# sensorev7V.net
KiCad netlist of a schematic drawn in EAGLE
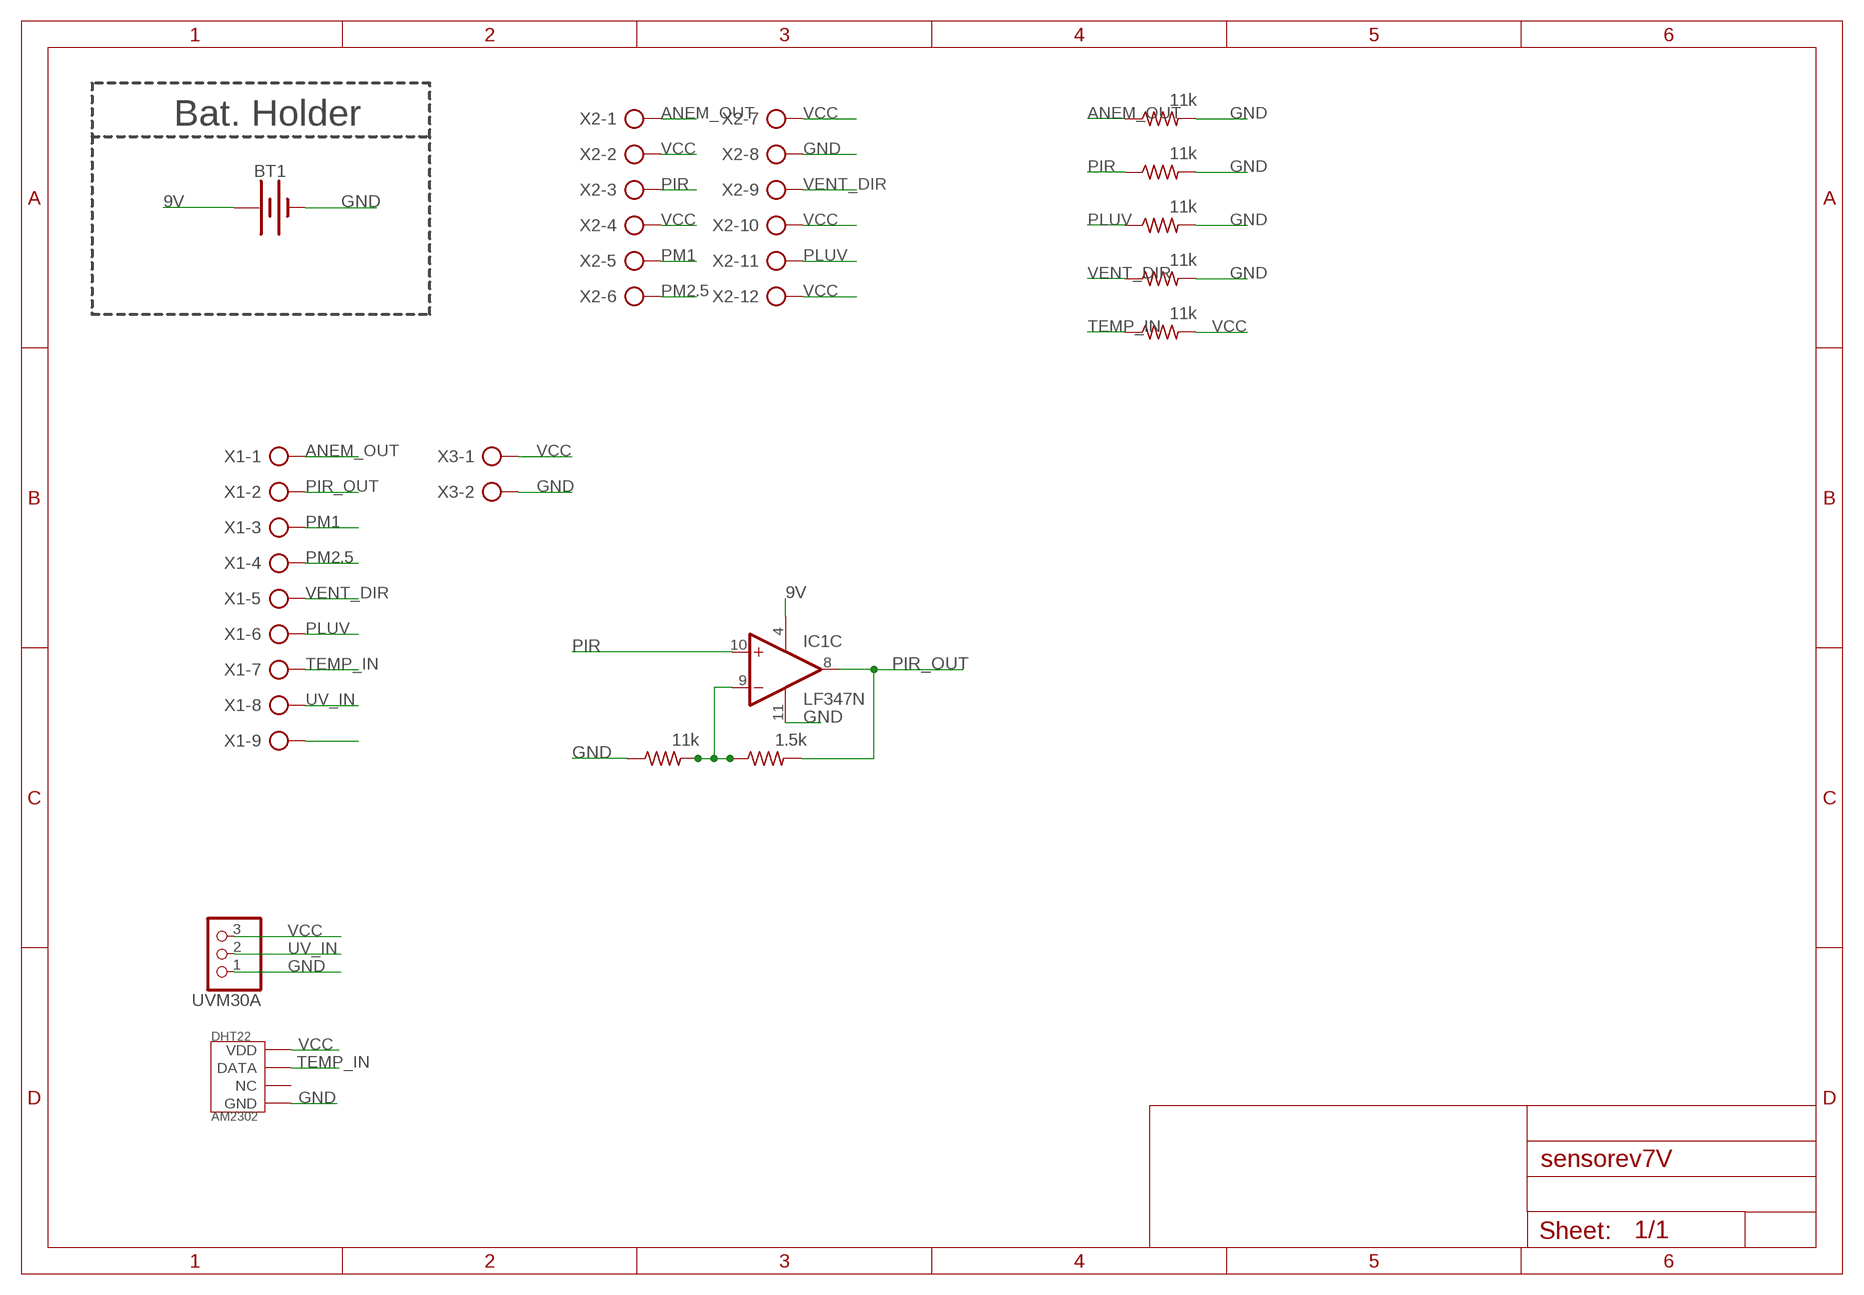
[diagram p0: schematic, sheet 1]

(export (version "E")
  (design (tool "Eeschema 10.0.6"))
  (components
    (comp (ref "BT1")
      (value "BATTERY-9V")
      (footprint "eagle-import:BATTCON_9V")
      (libsource (lib "eagle-import") (part "BATTERY-9V"))
    )
    (comp (ref "DHT22")
      (value "AM2302")
      (footprint "eagle-import:SNR4-2.54-25.0X15.0X7.0MM")
      (libsource (lib "eagle-import") (part "TEM-HUM-AM2302(4P-25.0X15.0MM)"))
    )
    (comp (ref "IC1")
      (value "LF347N")
      (footprint "eagle-import:DIL14")
      (libsource (lib "eagle-import") (part "LF347N"))
    )
    (comp (ref "R1")
      (value "11k")
      (footprint "eagle-import:0204_7")
      (libsource (lib "eagle-import") (part "R-US_0204/7"))
    )
    (comp (ref "R2")
      (value "1.5k")
      (footprint "eagle-import:0204_7")
      (libsource (lib "eagle-import") (part "R-US_0204/7"))
    )
    (comp (ref "R3")
      (value "11k")
      (footprint "eagle-import:0204_7")
      (libsource (lib "eagle-import") (part "R-US_0204/7"))
    )
    (comp (ref "R4")
      (value "11k")
      (footprint "eagle-import:0204_7")
      (libsource (lib "eagle-import") (part "R-US_0204/7"))
    )
    (comp (ref "R5")
      (value "11k")
      (footprint "eagle-import:0204_7")
      (libsource (lib "eagle-import") (part "R-US_0204/7"))
    )
    (comp (ref "R6")
      (value "11k")
      (footprint "eagle-import:0204_7")
      (libsource (lib "eagle-import") (part "R-US_0204/7"))
    )
    (comp (ref "R7")
      (value "11k")
      (footprint "eagle-import:0204_7")
      (libsource (lib "eagle-import") (part "R-US_0204/7"))
    )
    (comp (ref "UVM30A")
      (value "PINHD-1X3/90")
      (footprint "eagle-import:1X03_90")
      (libsource (lib "eagle-import") (part "PINHD-1X3/90"))
    )
    (comp (ref "X1")
      (value "AK500/9")
      (footprint "eagle-import:AK500_9")
      (libsource (lib "eagle-import") (part "AK500/9"))
    )
    (comp (ref "X2")
      (value "AK500/12")
      (footprint "eagle-import:AK500_12")
      (libsource (lib "eagle-import") (part "AK500/12"))
    )
    (comp (ref "X3")
      (value "AK500/2")
      (footprint "eagle-import:AK500_2")
      (libsource (lib "eagle-import") (part "AK500/2"))
    )
  )
  (nets
    (net (code "1") (name "/9V") (class "Default")
      (node (ref "BT1") (pin "+") (pinfunction "+_+") (pintype "power_in"))
      (node (ref "IC1") (pin "4") (pinfunction "V+_4") (pintype "power_in"))
    )
    (net (code "2") (name "/ANEM_OUT") (class "Default")
      (node (ref "R3") (pin "1") (pinfunction "1_1") (pintype "passive"))
      (node (ref "X1") (pin "1") (pinfunction "KL_1") (pintype "passive"))
      (node (ref "X2") (pin "1") (pinfunction "KL_1") (pintype "passive"))
    )
    (net (code "3") (name "/GND") (class "Default")
      (node (ref "BT1") (pin "-") (pinfunction "-_-") (pintype "power_in"))
      (node (ref "DHT22") (pin "P$4") (pinfunction "GND_P$4") (pintype "power_in"))
      (node (ref "IC1") (pin "11") (pinfunction "V-_11") (pintype "power_in"))
      (node (ref "R1") (pin "1") (pinfunction "1_1") (pintype "passive"))
      (node (ref "R3") (pin "2") (pinfunction "2_2") (pintype "passive"))
      (node (ref "R4") (pin "2") (pinfunction "2_2") (pintype "passive"))
      (node (ref "R5") (pin "2") (pinfunction "2_2") (pintype "passive"))
      (node (ref "R6") (pin "2") (pinfunction "2_2") (pintype "passive"))
      (node (ref "UVM30A") (pin "1") (pinfunction "1_1") (pintype "passive"))
      (node (ref "X2") (pin "8") (pinfunction "KL_8") (pintype "passive"))
      (node (ref "X3") (pin "2") (pinfunction "KL_2") (pintype "passive"))
    )
    (net (code "4") (name "/PIR") (class "Default")
      (node (ref "IC1") (pin "10") (pinfunction "+IN_10") (pintype "input"))
      (node (ref "R4") (pin "1") (pinfunction "1_1") (pintype "passive"))
      (node (ref "X2") (pin "3") (pinfunction "KL_3") (pintype "passive"))
    )
    (net (code "5") (name "/PIR_OUT") (class "Default")
      (node (ref "IC1") (pin "8") (pinfunction "OUT_8") (pintype "output"))
      (node (ref "R2") (pin "2") (pinfunction "2_2") (pintype "passive"))
      (node (ref "X1") (pin "2") (pinfunction "KL_2") (pintype "passive"))
    )
    (net (code "6") (name "/PLUV") (class "Default")
      (node (ref "R5") (pin "1") (pinfunction "1_1") (pintype "passive"))
      (node (ref "X1") (pin "6") (pinfunction "KL_6") (pintype "passive"))
      (node (ref "X2") (pin "11") (pinfunction "KL_11") (pintype "passive"))
    )
    (net (code "7") (name "/PM1") (class "Default")
      (node (ref "X1") (pin "3") (pinfunction "KL_3") (pintype "passive"))
      (node (ref "X2") (pin "5") (pinfunction "KL_5") (pintype "passive"))
    )
    (net (code "8") (name "/PM2.5") (class "Default")
      (node (ref "X1") (pin "4") (pinfunction "KL_4") (pintype "passive"))
      (node (ref "X2") (pin "6") (pinfunction "KL_6") (pintype "passive"))
    )
    (net (code "9") (name "/TEMP_IN") (class "Default")
      (node (ref "DHT22") (pin "P$2") (pinfunction "DATA_P$2") (pintype "bidirectional"))
      (node (ref "R7") (pin "1") (pinfunction "1_1") (pintype "passive"))
      (node (ref "X1") (pin "7") (pinfunction "KL_7") (pintype "passive"))
    )
    (net (code "10") (name "/UV_IN") (class "Default")
      (node (ref "UVM30A") (pin "2") (pinfunction "2_2") (pintype "passive"))
      (node (ref "X1") (pin "8") (pinfunction "KL_8") (pintype "passive"))
    )
    (net (code "11") (name "/VCC") (class "Default")
      (node (ref "DHT22") (pin "P$1") (pinfunction "VDD_P$1") (pintype "power_in"))
      (node (ref "R7") (pin "2") (pinfunction "2_2") (pintype "passive"))
      (node (ref "UVM30A") (pin "3") (pinfunction "3_3") (pintype "passive"))
      (node (ref "X2") (pin "10") (pinfunction "KL_10") (pintype "passive"))
      (node (ref "X2") (pin "12") (pinfunction "KL_12") (pintype "passive"))
      (node (ref "X2") (pin "2") (pinfunction "KL_2") (pintype "passive"))
      (node (ref "X2") (pin "4") (pinfunction "KL_4") (pintype "passive"))
      (node (ref "X2") (pin "7") (pinfunction "KL_7") (pintype "passive"))
      (node (ref "X3") (pin "1") (pinfunction "KL_1") (pintype "passive"))
    )
    (net (code "12") (name "/VENT_DIR") (class "Default")
      (node (ref "R6") (pin "1") (pinfunction "1_1") (pintype "passive"))
      (node (ref "X1") (pin "5") (pinfunction "KL_5") (pintype "passive"))
      (node (ref "X2") (pin "9") (pinfunction "KL_9") (pintype "passive"))
    )
    (net (code "13") (name "Net-(IC1C--IN)") (class "Default")
      (node (ref "IC1") (pin "9") (pinfunction "-IN_9") (pintype "input"))
      (node (ref "R1") (pin "2") (pinfunction "2_2") (pintype "passive"))
      (node (ref "R2") (pin "1") (pinfunction "1_1") (pintype "passive"))
    )
    (net (code "14") (name "unconnected-(DHT22-NC-PadP$3)") (class "Default")
      (node (ref "DHT22") (pin "P$3") (pinfunction "NC_P$3") (pintype "no_connect"))
    )
    (net (code "15") (name "unconnected-(X1I-KL-Pad9)") (class "Default")
      (node (ref "X1") (pin "9") (pinfunction "KL_9") (pintype "passive"))
    )
  )
)
